# Boris_IO_1.net
KiCad netlist of a schematic drawn in Altium Designer
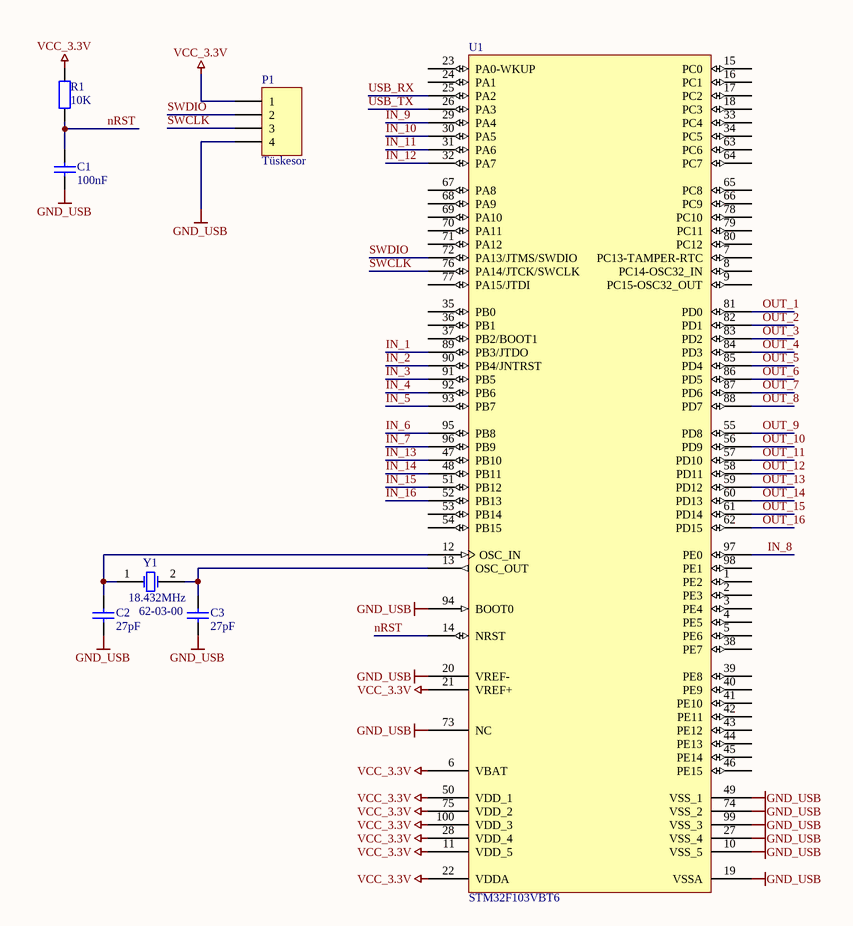
[diagram p0: Boris_IO_1.SchDoc]

(export (version "E")
  (design (tool "Eeschema 10.0.6"))
  (components
    (comp (ref "C1")
      (value "100nF")
      (footprint "0805_CAP")
      (description "Capacitor")
      (libsource (lib "Miscellaneous Devices") (part "Cap"))
    )
    (comp (ref "C2")
      (value "27pF")
      (footprint "0805_CAP")
      (description "Capacitor")
      (libsource (lib "Miscellaneous Devices") (part "Cap"))
    )
    (comp (ref "C3")
      (value "27pF")
      (footprint "0805_CAP")
      (description "Capacitor")
      (libsource (lib "Miscellaneous Devices") (part "Cap"))
    )
    (comp (ref "P1")
      (value "Tüskesor")
      (footprint "HDR1X4_2.54mmp")
      (description "Header, -Pin")
      (libsource (lib "MI_14") (part "Header 4"))
    )
    (comp (ref "R1")
      (value "10K")
      (footprint "0805_RES")
      (description "Resistor")
      (libsource (lib "Miscellaneous Devices") (part "Res2"))
    )
    (comp (ref "U1")
      (value "STM32F103VBT6")
      (footprint "LQFP100_N")
      (description "STM32 ARM-based 32-bit MCU with 64 Kbytes Flash, 100-pin LQFP, Industrial Temperature")
      (fields (field (name "PUBLISHER") "Altium Limited"))
      (libsource (lib "ST Microcontroller 32-Bit STM32") (part "STM32F103VBT6"))
    )
    (comp (ref "Y1")
      (value "18.432MHz")
      (footprint "SMU4")
      (description "Crystal Oscillator")
      (fields (field (name "CATALOG NUMBER") "62-03-00"))
      (libsource (lib "Miscellaneous Devices") (part "XTAL"))
    )
  )
  (nets
    (net (code "1") (name "/IN_1") (class "Default")
      (node (ref "U1") (pin "89") (pinfunction "PB3/JTDO_89") (pintype "bidirectional"))
    )
    (net (code "2") (name "/IN_2") (class "Default")
      (node (ref "U1") (pin "90") (pinfunction "PB4/JNTRST_90") (pintype "bidirectional"))
    )
    (net (code "3") (name "/IN_3") (class "Default")
      (node (ref "U1") (pin "91") (pinfunction "PB5_91") (pintype "bidirectional"))
    )
    (net (code "4") (name "/IN_4") (class "Default")
      (node (ref "U1") (pin "92") (pinfunction "PB6_92") (pintype "bidirectional"))
    )
    (net (code "5") (name "/IN_5") (class "Default")
      (node (ref "U1") (pin "93") (pinfunction "PB7_93") (pintype "bidirectional"))
    )
    (net (code "6") (name "/IN_6") (class "Default")
      (node (ref "U1") (pin "95") (pinfunction "PB8_95") (pintype "bidirectional"))
    )
    (net (code "7") (name "/IN_7") (class "Default")
      (node (ref "U1") (pin "96") (pinfunction "PB9_96") (pintype "bidirectional"))
    )
    (net (code "8") (name "/IN_8") (class "Default")
      (node (ref "U1") (pin "97") (pinfunction "PE0_97") (pintype "bidirectional"))
    )
    (net (code "9") (name "/IN_9") (class "Default")
      (node (ref "U1") (pin "29") (pinfunction "PA4_29") (pintype "bidirectional"))
    )
    (net (code "10") (name "/IN_10") (class "Default")
      (node (ref "U1") (pin "30") (pinfunction "PA5_30") (pintype "bidirectional"))
    )
    (net (code "11") (name "/IN_11") (class "Default")
      (node (ref "U1") (pin "31") (pinfunction "PA6_31") (pintype "bidirectional"))
    )
    (net (code "12") (name "/IN_12") (class "Default")
      (node (ref "U1") (pin "32") (pinfunction "PA7_32") (pintype "bidirectional"))
    )
    (net (code "13") (name "/IN_13") (class "Default")
      (node (ref "U1") (pin "47") (pinfunction "PB10_47") (pintype "bidirectional"))
    )
    (net (code "14") (name "/IN_14") (class "Default")
      (node (ref "U1") (pin "48") (pinfunction "PB11_48") (pintype "bidirectional"))
    )
    (net (code "15") (name "/IN_15") (class "Default")
      (node (ref "U1") (pin "51") (pinfunction "PB12_51") (pintype "bidirectional"))
    )
    (net (code "16") (name "/IN_16") (class "Default")
      (node (ref "U1") (pin "52") (pinfunction "PB13_52") (pintype "bidirectional"))
    )
    (net (code "17") (name "/OUT_1") (class "Default")
      (node (ref "U1") (pin "81") (pinfunction "PD0_81") (pintype "bidirectional"))
    )
    (net (code "18") (name "/OUT_2") (class "Default")
      (node (ref "U1") (pin "82") (pinfunction "PD1_82") (pintype "bidirectional"))
    )
    (net (code "19") (name "/OUT_3") (class "Default")
      (node (ref "U1") (pin "83") (pinfunction "PD2_83") (pintype "bidirectional"))
    )
    (net (code "20") (name "/OUT_4") (class "Default")
      (node (ref "U1") (pin "84") (pinfunction "PD3_84") (pintype "bidirectional"))
    )
    (net (code "21") (name "/OUT_5") (class "Default")
      (node (ref "U1") (pin "85") (pinfunction "PD4_85") (pintype "bidirectional"))
    )
    (net (code "22") (name "/OUT_6") (class "Default")
      (node (ref "U1") (pin "86") (pinfunction "PD5_86") (pintype "bidirectional"))
    )
    (net (code "23") (name "/OUT_7") (class "Default")
      (node (ref "U1") (pin "87") (pinfunction "PD6_87") (pintype "bidirectional"))
    )
    (net (code "24") (name "/OUT_8") (class "Default")
      (node (ref "U1") (pin "88") (pinfunction "PD7_88") (pintype "bidirectional"))
    )
    (net (code "25") (name "/OUT_9") (class "Default")
      (node (ref "U1") (pin "55") (pinfunction "PD8_55") (pintype "bidirectional"))
    )
    (net (code "26") (name "/OUT_10") (class "Default")
      (node (ref "U1") (pin "56") (pinfunction "PD9_56") (pintype "bidirectional"))
    )
    (net (code "27") (name "/OUT_11") (class "Default")
      (node (ref "U1") (pin "57") (pinfunction "PD10_57") (pintype "bidirectional"))
    )
    (net (code "28") (name "/OUT_12") (class "Default")
      (node (ref "U1") (pin "58") (pinfunction "PD11_58") (pintype "bidirectional"))
    )
    (net (code "29") (name "/OUT_13") (class "Default")
      (node (ref "U1") (pin "59") (pinfunction "PD12_59") (pintype "bidirectional"))
    )
    (net (code "30") (name "/OUT_14") (class "Default")
      (node (ref "U1") (pin "60") (pinfunction "PD13_60") (pintype "bidirectional"))
    )
    (net (code "31") (name "/OUT_15") (class "Default")
      (node (ref "U1") (pin "61") (pinfunction "PD14_61") (pintype "bidirectional"))
    )
    (net (code "32") (name "/OUT_16") (class "Default")
      (node (ref "U1") (pin "62") (pinfunction "PD15_62") (pintype "bidirectional"))
    )
    (net (code "33") (name "/SWCLK") (class "Default")
      (node (ref "P1") (pin "3") (pinfunction "3_3") (pintype "passive"))
      (node (ref "U1") (pin "76") (pinfunction "PA14/JTCK/SWCLK_76") (pintype "bidirectional"))
    )
    (net (code "34") (name "/SWDIO") (class "Default")
      (node (ref "P1") (pin "2") (pinfunction "2_2") (pintype "passive"))
      (node (ref "U1") (pin "72") (pinfunction "PA13/JTMS/SWDIO_72") (pintype "bidirectional"))
    )
    (net (code "35") (name "/USB_RX") (class "Default")
      (node (ref "U1") (pin "25") (pinfunction "PA2_25") (pintype "bidirectional"))
    )
    (net (code "36") (name "/USB_TX") (class "Default")
      (node (ref "U1") (pin "26") (pinfunction "PA3_26") (pintype "bidirectional"))
    )
    (net (code "37") (name "/nRST") (class "Default")
      (node (ref "C1") (pin "1") (pinfunction "1_1") (pintype "passive"))
      (node (ref "R1") (pin "1") (pinfunction "1_1") (pintype "passive"))
      (node (ref "U1") (pin "14") (pinfunction "NRST_14") (pintype "bidirectional"))
    )
    (net (code "38") (name "GND_USB") (class "Default")
      (node (ref "C1") (pin "2") (pinfunction "2_2") (pintype "passive"))
      (node (ref "C2") (pin "1") (pinfunction "1_1") (pintype "passive"))
      (node (ref "C3") (pin "1") (pinfunction "1_1") (pintype "passive"))
      (node (ref "P1") (pin "4") (pinfunction "4_4") (pintype "passive"))
      (node (ref "U1") (pin "10") (pinfunction "VSS_5_10") (pintype "power_in"))
      (node (ref "U1") (pin "19") (pinfunction "VSSA_19") (pintype "power_in"))
      (node (ref "U1") (pin "20") (pinfunction "VREF-_20") (pintype "power_in"))
      (node (ref "U1") (pin "27") (pinfunction "VSS_4_27") (pintype "power_in"))
      (node (ref "U1") (pin "49") (pinfunction "VSS_1_49") (pintype "power_in"))
      (node (ref "U1") (pin "73") (pinfunction "NC_73") (pintype "passive"))
      (node (ref "U1") (pin "74") (pinfunction "VSS_2_74") (pintype "power_in"))
      (node (ref "U1") (pin "94") (pinfunction "BOOT0_94") (pintype "input"))
      (node (ref "U1") (pin "99") (pinfunction "VSS_3_99") (pintype "power_in"))
    )
    (net (code "39") (name "Net-(U1-OSC_IN)") (class "Default")
      (node (ref "C2") (pin "2") (pinfunction "2_2") (pintype "passive"))
      (node (ref "U1") (pin "12") (pinfunction "OSC_IN_12") (pintype "input"))
      (node (ref "Y1") (pin "1") (pinfunction "OSC1_1") (pintype "passive"))
    )
    (net (code "40") (name "Net-(U1-OSC_OUT)") (class "Default")
      (node (ref "C3") (pin "2") (pinfunction "2_2") (pintype "passive"))
      (node (ref "U1") (pin "13") (pinfunction "OSC_OUT_13") (pintype "output"))
      (node (ref "Y1") (pin "2") (pinfunction "OSC2_2") (pintype "passive"))
    )
    (net (code "41") (name "VCC_3.3V") (class "Default")
      (node (ref "P1") (pin "1") (pinfunction "1_1") (pintype "passive"))
      (node (ref "R1") (pin "2") (pinfunction "2_2") (pintype "passive"))
      (node (ref "U1") (pin "100") (pinfunction "VDD_3_100") (pintype "power_in"))
      (node (ref "U1") (pin "11") (pinfunction "VDD_5_11") (pintype "power_in"))
      (node (ref "U1") (pin "21") (pinfunction "VREF+_21") (pintype "power_in"))
      (node (ref "U1") (pin "22") (pinfunction "VDDA_22") (pintype "power_in"))
      (node (ref "U1") (pin "28") (pinfunction "VDD_4_28") (pintype "power_in"))
      (node (ref "U1") (pin "50") (pinfunction "VDD_1_50") (pintype "power_in"))
      (node (ref "U1") (pin "6") (pinfunction "VBAT_6") (pintype "power_in"))
      (node (ref "U1") (pin "75") (pinfunction "VDD_2_75") (pintype "power_in"))
    )
    (net (code "42") (name "unconnected-(U1-PA0-WKUP-Pad23)") (class "Default")
      (node (ref "U1") (pin "23") (pinfunction "PA0-WKUP_23") (pintype "bidirectional"))
    )
    (net (code "43") (name "unconnected-(U1-PA1-Pad24)") (class "Default")
      (node (ref "U1") (pin "24") (pinfunction "PA1_24") (pintype "bidirectional"))
    )
    (net (code "44") (name "unconnected-(U1-PA8-Pad67)") (class "Default")
      (node (ref "U1") (pin "67") (pinfunction "PA8_67") (pintype "bidirectional"))
    )
    (net (code "45") (name "unconnected-(U1-PA9-Pad68)") (class "Default")
      (node (ref "U1") (pin "68") (pinfunction "PA9_68") (pintype "bidirectional"))
    )
    (net (code "46") (name "unconnected-(U1-PA10-Pad69)") (class "Default")
      (node (ref "U1") (pin "69") (pinfunction "PA10_69") (pintype "bidirectional"))
    )
    (net (code "47") (name "unconnected-(U1-PA11-Pad70)") (class "Default")
      (node (ref "U1") (pin "70") (pinfunction "PA11_70") (pintype "bidirectional"))
    )
    (net (code "48") (name "unconnected-(U1-PA12-Pad71)") (class "Default")
      (node (ref "U1") (pin "71") (pinfunction "PA12_71") (pintype "bidirectional"))
    )
    (net (code "49") (name "unconnected-(U1-PA15{slash}JTDI-Pad77)") (class "Default")
      (node (ref "U1") (pin "77") (pinfunction "PA15/JTDI_77") (pintype "bidirectional"))
    )
    (net (code "50") (name "unconnected-(U1-PB0-Pad35)") (class "Default")
      (node (ref "U1") (pin "35") (pinfunction "PB0_35") (pintype "bidirectional"))
    )
    (net (code "51") (name "unconnected-(U1-PB1-Pad36)") (class "Default")
      (node (ref "U1") (pin "36") (pinfunction "PB1_36") (pintype "bidirectional"))
    )
    (net (code "52") (name "unconnected-(U1-PB2{slash}BOOT1-Pad37)") (class "Default")
      (node (ref "U1") (pin "37") (pinfunction "PB2/BOOT1_37") (pintype "bidirectional"))
    )
    (net (code "53") (name "unconnected-(U1-PB14-Pad53)") (class "Default")
      (node (ref "U1") (pin "53") (pinfunction "PB14_53") (pintype "bidirectional"))
    )
    (net (code "54") (name "unconnected-(U1-PB15-Pad54)") (class "Default")
      (node (ref "U1") (pin "54") (pinfunction "PB15_54") (pintype "bidirectional"))
    )
    (net (code "55") (name "unconnected-(U1-PC0-Pad15)") (class "Default")
      (node (ref "U1") (pin "15") (pinfunction "PC0_15") (pintype "bidirectional"))
    )
    (net (code "56") (name "unconnected-(U1-PC1-Pad16)") (class "Default")
      (node (ref "U1") (pin "16") (pinfunction "PC1_16") (pintype "bidirectional"))
    )
    (net (code "57") (name "unconnected-(U1-PC2-Pad17)") (class "Default")
      (node (ref "U1") (pin "17") (pinfunction "PC2_17") (pintype "bidirectional"))
    )
    (net (code "58") (name "unconnected-(U1-PC3-Pad18)") (class "Default")
      (node (ref "U1") (pin "18") (pinfunction "PC3_18") (pintype "bidirectional"))
    )
    (net (code "59") (name "unconnected-(U1-PC4-Pad33)") (class "Default")
      (node (ref "U1") (pin "33") (pinfunction "PC4_33") (pintype "bidirectional"))
    )
    (net (code "60") (name "unconnected-(U1-PC5-Pad34)") (class "Default")
      (node (ref "U1") (pin "34") (pinfunction "PC5_34") (pintype "bidirectional"))
    )
    (net (code "61") (name "unconnected-(U1-PC6-Pad63)") (class "Default")
      (node (ref "U1") (pin "63") (pinfunction "PC6_63") (pintype "bidirectional"))
    )
    (net (code "62") (name "unconnected-(U1-PC7-Pad64)") (class "Default")
      (node (ref "U1") (pin "64") (pinfunction "PC7_64") (pintype "bidirectional"))
    )
    (net (code "63") (name "unconnected-(U1-PC8-Pad65)") (class "Default")
      (node (ref "U1") (pin "65") (pinfunction "PC8_65") (pintype "bidirectional"))
    )
    (net (code "64") (name "unconnected-(U1-PC9-Pad66)") (class "Default")
      (node (ref "U1") (pin "66") (pinfunction "PC9_66") (pintype "bidirectional"))
    )
    (net (code "65") (name "unconnected-(U1-PC10-Pad78)") (class "Default")
      (node (ref "U1") (pin "78") (pinfunction "PC10_78") (pintype "bidirectional"))
    )
    (net (code "66") (name "unconnected-(U1-PC11-Pad79)") (class "Default")
      (node (ref "U1") (pin "79") (pinfunction "PC11_79") (pintype "bidirectional"))
    )
    (net (code "67") (name "unconnected-(U1-PC12-Pad80)") (class "Default")
      (node (ref "U1") (pin "80") (pinfunction "PC12_80") (pintype "bidirectional"))
    )
    (net (code "68") (name "unconnected-(U1-PC13-TAMPER-RTC-Pad7)") (class "Default")
      (node (ref "U1") (pin "7") (pinfunction "PC13-TAMPER-RTC_7") (pintype "bidirectional"))
    )
    (net (code "69") (name "unconnected-(U1-PC14-OSC32_IN-Pad8)") (class "Default")
      (node (ref "U1") (pin "8") (pinfunction "PC14-OSC32_IN_8") (pintype "bidirectional"))
    )
    (net (code "70") (name "unconnected-(U1-PC15-OSC32_OUT-Pad9)") (class "Default")
      (node (ref "U1") (pin "9") (pinfunction "PC15-OSC32_OUT_9") (pintype "bidirectional"))
    )
    (net (code "71") (name "unconnected-(U1-PE1-Pad98)") (class "Default")
      (node (ref "U1") (pin "98") (pinfunction "PE1_98") (pintype "bidirectional"))
    )
    (net (code "72") (name "unconnected-(U1-PE2-Pad1)") (class "Default")
      (node (ref "U1") (pin "1") (pinfunction "PE2_1") (pintype "bidirectional"))
    )
    (net (code "73") (name "unconnected-(U1-PE3-Pad2)") (class "Default")
      (node (ref "U1") (pin "2") (pinfunction "PE3_2") (pintype "bidirectional"))
    )
    (net (code "74") (name "unconnected-(U1-PE4-Pad3)") (class "Default")
      (node (ref "U1") (pin "3") (pinfunction "PE4_3") (pintype "bidirectional"))
    )
    (net (code "75") (name "unconnected-(U1-PE5-Pad4)") (class "Default")
      (node (ref "U1") (pin "4") (pinfunction "PE5_4") (pintype "bidirectional"))
    )
    (net (code "76") (name "unconnected-(U1-PE6-Pad5)") (class "Default")
      (node (ref "U1") (pin "5") (pinfunction "PE6_5") (pintype "bidirectional"))
    )
    (net (code "77") (name "unconnected-(U1-PE7-Pad38)") (class "Default")
      (node (ref "U1") (pin "38") (pinfunction "PE7_38") (pintype "bidirectional"))
    )
    (net (code "78") (name "unconnected-(U1-PE8-Pad39)") (class "Default")
      (node (ref "U1") (pin "39") (pinfunction "PE8_39") (pintype "bidirectional"))
    )
    (net (code "79") (name "unconnected-(U1-PE9-Pad40)") (class "Default")
      (node (ref "U1") (pin "40") (pinfunction "PE9_40") (pintype "bidirectional"))
    )
    (net (code "80") (name "unconnected-(U1-PE10-Pad41)") (class "Default")
      (node (ref "U1") (pin "41") (pinfunction "PE10_41") (pintype "bidirectional"))
    )
    (net (code "81") (name "unconnected-(U1-PE11-Pad42)") (class "Default")
      (node (ref "U1") (pin "42") (pinfunction "PE11_42") (pintype "bidirectional"))
    )
    (net (code "82") (name "unconnected-(U1-PE12-Pad43)") (class "Default")
      (node (ref "U1") (pin "43") (pinfunction "PE12_43") (pintype "bidirectional"))
    )
    (net (code "83") (name "unconnected-(U1-PE13-Pad44)") (class "Default")
      (node (ref "U1") (pin "44") (pinfunction "PE13_44") (pintype "bidirectional"))
    )
    (net (code "84") (name "unconnected-(U1-PE14-Pad45)") (class "Default")
      (node (ref "U1") (pin "45") (pinfunction "PE14_45") (pintype "bidirectional"))
    )
    (net (code "85") (name "unconnected-(U1-PE15-Pad46)") (class "Default")
      (node (ref "U1") (pin "46") (pinfunction "PE15_46") (pintype "bidirectional"))
    )
  )
)
